# rs485-interface.net
KiCad netlist of a schematic drawn in Altium Designer
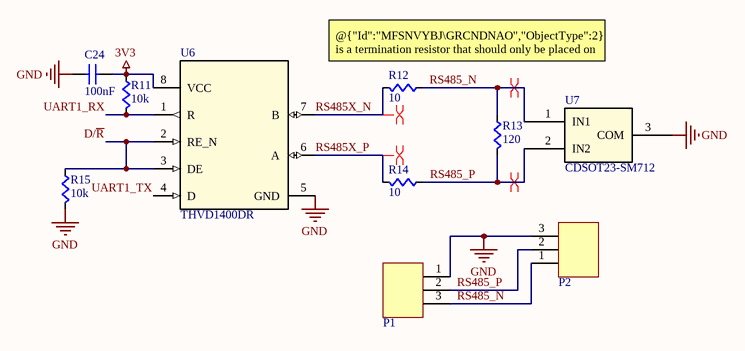
[diagram p0: rs485-interface.SchDoc]

(export (version "E")
  (design (tool "Eeschema 10.0.6"))
  (components
    (comp (ref "C24")
      (value "100nF")
      (footprint "CAPC0603")
      (fields (field (name "Comment") "Cap"))
      (libsource (lib "Passives") (part "Cap"))
    )
    (comp (ref "P1")
      (value "3pos RA sherlock connector")
      (footprint "MOLEX-HDR-1X3-SHERLOCK-RA")
      (description "Header, Molex, 2mm Pitch Sherlock Header, Single Row, Right Angle 3 Circuits, Length 3.3mm")
      (fields
        (field (name "MANUFACTURER PART NUMBER") "35363-0360")
        (field (name "MANUFACTURER") "Molex Connector Corporation")
      )
      (libsource (lib "") (part "MOLEX-HDR-1x3-SHERLOCK_RA_1"))
    )
    (comp (ref "P2")
      (value "3pos RA sherlock connector")
      (footprint "MOLEX-HDR-1X3-SHERLOCK-RA")
      (description "Header, Molex, 2mm Pitch Sherlock Header, Single Row, Right Angle 3 Circuits, Length 3.3mm")
      (fields
        (field (name "MANUFACTURER PART NUMBER") "35363-0360")
        (field (name "MANUFACTURER") "Molex Connector Corporation")
      )
      (libsource (lib "Connectors") (part "MOLEX-HDR-1x3-SHERLOCK_RA"))
    )
    (comp (ref "R11")
      (value "10k")
      (footprint "RES0603")
      (description "SMD, RES0603")
      (fields (field (name "Comment") "Res"))
      (libsource (lib "Passives") (part "Res"))
    )
    (comp (ref "R12")
      (value "10")
      (footprint "RES0603")
      (description "SMD, RES0603")
      (fields (field (name "Comment") "Res"))
      (libsource (lib "Passives") (part "Res"))
    )
    (comp (ref "R13")
      (value "120")
      (footprint "RES0603")
      (description "SMD, RES0603")
      (fields (field (name "Comment") "Res"))
      (libsource (lib "Passives") (part "Res"))
    )
    (comp (ref "R14")
      (value "10")
      (footprint "RES0603")
      (description "SMD, RES0603")
      (fields (field (name "Comment") "Res"))
      (libsource (lib "Passives") (part "Res"))
    )
    (comp (ref "R15")
      (value "10k")
      (footprint "RES0603")
      (description "SMD, RES0603")
      (fields (field (name "Comment") "Res"))
      (libsource (lib "Passives") (part "Res"))
    )
    (comp (ref "U6")
      (value "THVD1400DR")
      (footprint "D0008B-MFG")
      (fields (field (name "COPYRIGHT") "Copyright (C) 2026 Ultra Librarian. All rights reserved."))
      (libsource (lib "Alexandria") (part "THVD1400DR"))
    )
    (comp (ref "U7")
      (value "CDSOT23-SM712")
      (footprint "SOT_SM712")
      (description "TVS DIODE 12VWM 7VWM SOT23-3")
      (fields (field (name "COPYRIGHT") "Copyright (C) 2026 Ultra Librarian. All rights reserved."))
      (libsource (lib "Alexandria") (part "CDSOT23-SM712"))
    )
  )
  (nets
    (net (code "1") (name "/D{slash}~{R}") (class "Default")
      (node (ref "R15") (pin "2") (pinfunction "B_2") (pintype "passive"))
      (node (ref "U6") (pin "2") (pinfunction "RE_N_2") (pintype "input"))
      (node (ref "U6") (pin "3") (pinfunction "DE_3") (pintype "input"))
    )
    (net (code "2") (name "/RS485X_N") (class "Default")
      (node (ref "R12") (pin "1") (pinfunction "A_1") (pintype "passive"))
      (node (ref "U6") (pin "7") (pinfunction "B_7") (pintype "bidirectional"))
    )
    (net (code "3") (name "/RS485X_P") (class "Default")
      (node (ref "R14") (pin "1") (pinfunction "A_1") (pintype "passive"))
      (node (ref "U6") (pin "6") (pinfunction "A_6") (pintype "bidirectional"))
    )
    (net (code "4") (name "/RS485_N") (class "Default")
      (node (ref "P1") (pin "3") (pinfunction "3_3") (pintype "passive"))
      (node (ref "P2") (pin "1") (pinfunction "1_1") (pintype "passive"))
      (node (ref "R12") (pin "2") (pinfunction "B_2") (pintype "passive"))
      (node (ref "R13") (pin "2") (pinfunction "B_2") (pintype "passive"))
      (node (ref "U7") (pin "1") (pinfunction "IN1_1") (pintype "passive"))
    )
    (net (code "5") (name "/RS485_P") (class "Default")
      (node (ref "P1") (pin "2") (pinfunction "2_2") (pintype "passive"))
      (node (ref "P2") (pin "2") (pinfunction "2_2") (pintype "passive"))
      (node (ref "R13") (pin "1") (pinfunction "A_1") (pintype "passive"))
      (node (ref "R14") (pin "2") (pinfunction "B_2") (pintype "passive"))
      (node (ref "U7") (pin "2") (pinfunction "IN2_2") (pintype "passive"))
    )
    (net (code "6") (name "/UART1_RX") (class "Default")
      (node (ref "R11") (pin "1") (pinfunction "A_1") (pintype "passive"))
      (node (ref "U6") (pin "1") (pinfunction "R_1") (pintype "output"))
    )
    (net (code "7") (name "/UART1_TX") (class "Default")
      (node (ref "U6") (pin "4") (pinfunction "D_4") (pintype "input"))
    )
    (net (code "8") (name "3V3") (class "Default")
      (node (ref "C24") (pin "2") (pinfunction "B_2") (pintype "passive"))
      (node (ref "R11") (pin "2") (pinfunction "B_2") (pintype "passive"))
      (node (ref "U6") (pin "8") (pinfunction "VCC_8") (pintype "power_in"))
    )
    (net (code "9") (name "GND") (class "Default")
      (node (ref "C24") (pin "1") (pinfunction "A_1") (pintype "passive"))
      (node (ref "P1") (pin "1") (pinfunction "1_1") (pintype "passive"))
      (node (ref "P2") (pin "3") (pinfunction "3_3") (pintype "passive"))
      (node (ref "R15") (pin "1") (pinfunction "A_1") (pintype "passive"))
      (node (ref "U6") (pin "5") (pinfunction "GND_5") (pintype "power_in"))
      (node (ref "U7") (pin "3") (pinfunction "COM_3") (pintype "passive"))
    )
  )
)
